# Schematic.net
KiCad netlist of a schematic drawn in EAGLE
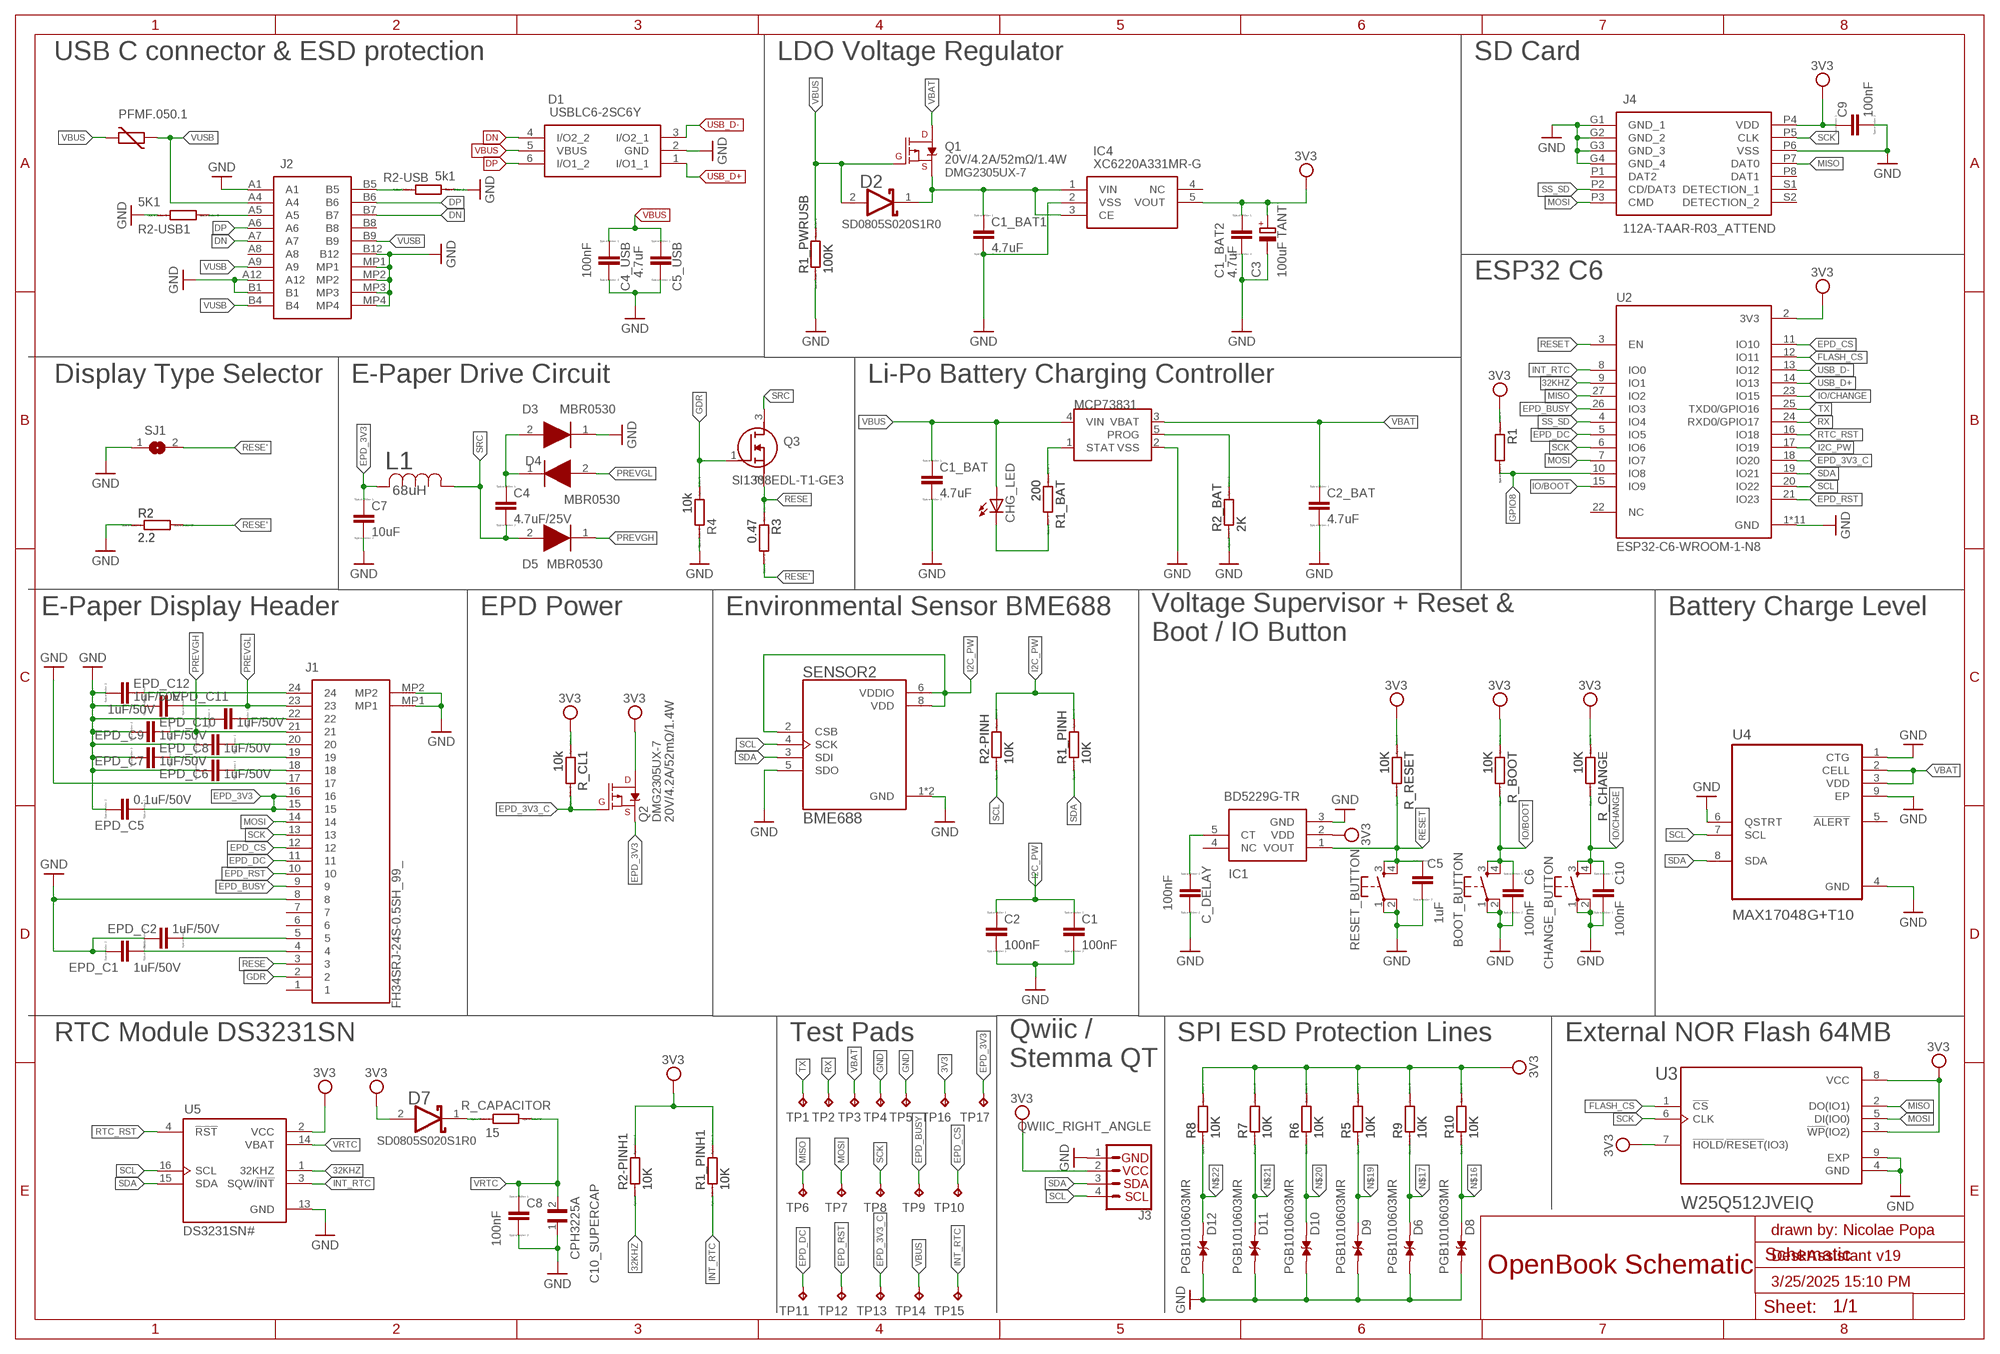
[diagram p0: schematic, sheet 1]

(export (version "E")
  (design (tool "Eeschema 10.0.6"))
  (components
    (comp (ref "BOOT_BUTTON")
      (value "BUTTON_CUSYOMV1")
      (footprint "eagle-import:MYBUTTON")
      (libsource (lib "eagle-import") (part "BUTTON_CUSYOMV1"))
    )
    (comp (ref "C1")
      (value "100nF")
      (footprint "eagle-import:EAGLE-LTSPICE_C0402")
      (libsource (lib "eagle-import") (part "EAGLE-LTSPICE_CC0402"))
    )
    (comp (ref "C1_BAT")
      (value "4.7uF")
      (footprint "eagle-import:EAGLE-LTSPICE_C0402")
      (libsource (lib "eagle-import") (part "EAGLE-LTSPICE_CC0402"))
    )
    (comp (ref "C1_BAT1")
      (value "4.7uF")
      (footprint "eagle-import:EAGLE-LTSPICE_C0402")
      (libsource (lib "eagle-import") (part "EAGLE-LTSPICE_CC0402"))
    )
    (comp (ref "C1_BAT2")
      (value "4.7uF")
      (footprint "eagle-import:EAGLE-LTSPICE_C0402")
      (libsource (lib "eagle-import") (part "EAGLE-LTSPICE_CC0402"))
    )
    (comp (ref "C2")
      (value "100nF")
      (footprint "eagle-import:EAGLE-LTSPICE_C0402")
      (libsource (lib "eagle-import") (part "EAGLE-LTSPICE_CC0402"))
    )
    (comp (ref "C2_BAT")
      (value "4.7uF")
      (footprint "eagle-import:EAGLE-LTSPICE_C0402")
      (libsource (lib "eagle-import") (part "EAGLE-LTSPICE_CC0402"))
    )
    (comp (ref "C3")
      (value "100uF TANT")
      (footprint "eagle-import:RCL_CT3528")
      (libsource (lib "eagle-import") (part "RCL_CPOL-EUCT3528"))
    )
    (comp (ref "C4")
      (value "4.7uF/25V")
      (footprint "eagle-import:EAGLE-LTSPICE_C0402")
      (libsource (lib "eagle-import") (part "EAGLE-LTSPICE_CC0402"))
    )
    (comp (ref "C4_USB")
      (value "100nF")
      (footprint "eagle-import:EAGLE-LTSPICE_C0402")
      (libsource (lib "eagle-import") (part "EAGLE-LTSPICE_CC0402"))
    )
    (comp (ref "C5")
      (value "1uF")
      (footprint "eagle-import:EAGLE-LTSPICE_C0402")
      (libsource (lib "eagle-import") (part "EAGLE-LTSPICE_CC0402"))
    )
    (comp (ref "C5_USB")
      (value "4.7uF")
      (footprint "eagle-import:EAGLE-LTSPICE_C0402")
      (libsource (lib "eagle-import") (part "EAGLE-LTSPICE_CC0402"))
    )
    (comp (ref "C6")
      (value "100nF")
      (footprint "eagle-import:EAGLE-LTSPICE_C0402")
      (libsource (lib "eagle-import") (part "EAGLE-LTSPICE_CC0402"))
    )
    (comp (ref "C7")
      (value "10uF")
      (footprint "eagle-import:EAGLE-LTSPICE_C0402")
      (libsource (lib "eagle-import") (part "EAGLE-LTSPICE_CC0402"))
    )
    (comp (ref "C8")
      (value "100nF")
      (footprint "eagle-import:EAGLE-LTSPICE_C0402")
      (libsource (lib "eagle-import") (part "EAGLE-LTSPICE_CC0402"))
    )
    (comp (ref "C9")
      (value "100nF")
      (footprint "eagle-import:ESP32_WROVER_EAGLE-LTSPICE_C0402")
      (libsource (lib "eagle-import") (part "ESP32_WROVER_EAGLE-LTSPICE_CC0402"))
    )
    (comp (ref "C10")
      (value "100nF")
      (footprint "eagle-import:EAGLE-LTSPICE_C0402")
      (libsource (lib "eagle-import") (part "EAGLE-LTSPICE_CC0402"))
    )
    (comp (ref "C10_SUPERCAP")
      (value "CPH3225A")
      (footprint "eagle-import:CAPCP3225X100N")
      (fields (field (name "MF") "Seiko Instruments"))
      (libsource (lib "eagle-import") (part "CPH3225A"))
    )
    (comp (ref "CHANGE_BUTTON")
      (value "BUTTON_CUSYOMV1")
      (footprint "eagle-import:MYBUTTON")
      (libsource (lib "eagle-import") (part "BUTTON_CUSYOMV1"))
    )
    (comp (ref "CHG_LED")
      (value "ADAFRUIT_LEDCHIP-LED0603")
      (footprint "eagle-import:ADAFRUIT_CHIP-LED0603")
      (libsource (lib "eagle-import") (part "ADAFRUIT_LEDCHIP-LED0603"))
    )
    (comp (ref "C_DELAY")
      (value "100nF")
      (footprint "eagle-import:EAGLE-LTSPICE_C0402")
      (libsource (lib "eagle-import") (part "EAGLE-LTSPICE_CC0402"))
    )
    (comp (ref "D1")
      (value "USBLC6-2SC6Y")
      (footprint "eagle-import:SOT95P280X145-6N")
      (fields (field (name "MF") "STMicroelectronics"))
      (libsource (lib "eagle-import") (part "USBLC6-2SC6Y"))
    )
    (comp (ref "D2")
      (value "ESP32_WROVER_AVX---SD0805S020S1R0_AVX_SD0805S020S1R0_0_0AVX_SD0805S020S1R0_0_0")
      (footprint "eagle-import:ESP32_WROVER_AVX---SD0805S020S1R0_AVX_SD0805S020S1R0_0")
      (fields
        (field (name "DIGIKEY_PART_NUMBER") "478-7800-1-ND")
        (field (name "MF") "AVX")
        (field (name "MOUSER_PART_NUMBER") "581-SD0805S020S1R0")
        (field (name "MANUFACTURER") "SD0805S020S1R0")
      )
      (libsource (lib "eagle-import") (part "ESP32_WROVER_AVX---SD0805S020S1R0_AVX_SD0805S020S1R0_0_0AVX_SD0805S020S1R0_0_0"))
    )
    (comp (ref "D3")
      (value "MBR0530")
      (footprint "eagle-import:SOD3716X135N")
      (fields (field (name "MF") "ON Semiconductor"))
      (libsource (lib "eagle-import") (part "MBR0530"))
    )
    (comp (ref "D4")
      (value "MBR0530")
      (footprint "eagle-import:SOD3716X135N")
      (fields (field (name "MF") "ON Semiconductor"))
      (libsource (lib "eagle-import") (part "MBR0530"))
    )
    (comp (ref "D5")
      (value "MBR0530")
      (footprint "eagle-import:SOD3716X135N")
      (fields (field (name "MF") "ON Semiconductor"))
      (libsource (lib "eagle-import") (part "MBR0530"))
    )
    (comp (ref "D6")
      (value "PGB1010603MR")
      (footprint "eagle-import:DIOC1608X36N")
      (fields (field (name "MF") "Littelfuse Inc."))
      (libsource (lib "eagle-import") (part "PGB1010603MR"))
    )
    (comp (ref "D7")
      (value "SD0805S020S1R0")
      (footprint "eagle-import:ESP32_WROVER_AVX---SD0805S020S1R0_AVX_SD0805S020S1R0_0")
      (fields
        (field (name "DIGIKEY_PART_NUMBER") "478-7800-1-ND")
        (field (name "MF") "AVX")
        (field (name "MOUSER_PART_NUMBER") "581-SD0805S020S1R0")
        (field (name "MANUFACTURER") "SD0805S020S1R0")
      )
      (libsource (lib "eagle-import") (part "ESP32_WROVER_AVX---SD0805S020S1R0_AVX_SD0805S020S1R0_0_0AVX_SD0805S020S1R0_0_0"))
    )
    (comp (ref "D8")
      (value "PGB1010603MR")
      (footprint "eagle-import:DIOC1608X36N")
      (fields (field (name "MF") "Littelfuse Inc."))
      (libsource (lib "eagle-import") (part "PGB1010603MR"))
    )
    (comp (ref "D9")
      (value "PGB1010603MR")
      (footprint "eagle-import:DIOC1608X36N")
      (fields (field (name "MF") "Littelfuse Inc."))
      (libsource (lib "eagle-import") (part "PGB1010603MR"))
    )
    (comp (ref "D10")
      (value "PGB1010603MR")
      (footprint "eagle-import:DIOC1608X36N")
      (fields (field (name "MF") "Littelfuse Inc."))
      (libsource (lib "eagle-import") (part "PGB1010603MR"))
    )
    (comp (ref "D11")
      (value "PGB1010603MR")
      (footprint "eagle-import:DIOC1608X36N")
      (fields (field (name "MF") "Littelfuse Inc."))
      (libsource (lib "eagle-import") (part "PGB1010603MR"))
    )
    (comp (ref "D12")
      (value "PGB1010603MR")
      (footprint "eagle-import:DIOC1608X36N")
      (fields (field (name "MF") "Littelfuse Inc."))
      (libsource (lib "eagle-import") (part "PGB1010603MR"))
    )
    (comp (ref "EPD_C1")
      (value "1uF/50V")
      (footprint "eagle-import:EAGLE-LTSPICE_C0402")
      (libsource (lib "eagle-import") (part "EAGLE-LTSPICE_CC0402"))
    )
    (comp (ref "EPD_C2")
      (value "1uF/50V")
      (footprint "eagle-import:EAGLE-LTSPICE_C0402")
      (libsource (lib "eagle-import") (part "EAGLE-LTSPICE_CC0402"))
    )
    (comp (ref "EPD_C5")
      (value "0.1uF/50V")
      (footprint "eagle-import:EAGLE-LTSPICE_C0402")
      (libsource (lib "eagle-import") (part "EAGLE-LTSPICE_CC0402"))
    )
    (comp (ref "EPD_C6")
      (value "1uF/50V")
      (footprint "eagle-import:EAGLE-LTSPICE_C0402")
      (libsource (lib "eagle-import") (part "EAGLE-LTSPICE_CC0402"))
    )
    (comp (ref "EPD_C7")
      (value "1uF/50V")
      (footprint "eagle-import:EAGLE-LTSPICE_C0402")
      (libsource (lib "eagle-import") (part "EAGLE-LTSPICE_CC0402"))
    )
    (comp (ref "EPD_C8")
      (value "1uF/50V")
      (footprint "eagle-import:EAGLE-LTSPICE_C0402")
      (libsource (lib "eagle-import") (part "EAGLE-LTSPICE_CC0402"))
    )
    (comp (ref "EPD_C9")
      (value "1uF/50V")
      (footprint "eagle-import:EAGLE-LTSPICE_C0402")
      (libsource (lib "eagle-import") (part "EAGLE-LTSPICE_CC0402"))
    )
    (comp (ref "EPD_C10")
      (value "1uF/50V")
      (footprint "eagle-import:EAGLE-LTSPICE_C0402")
      (libsource (lib "eagle-import") (part "EAGLE-LTSPICE_CC0402"))
    )
    (comp (ref "EPD_C11")
      (value "1uF/50V")
      (footprint "eagle-import:EAGLE-LTSPICE_C0402")
      (libsource (lib "eagle-import") (part "EAGLE-LTSPICE_CC0402"))
    )
    (comp (ref "EPD_C12")
      (value "1uF/50V")
      (footprint "eagle-import:EAGLE-LTSPICE_C0402")
      (libsource (lib "eagle-import") (part "EAGLE-LTSPICE_CC0402"))
    )
    (comp (ref "IC1")
      (value "BD5229G-TR")
      (footprint "eagle-import:SOT95P280X125-5N")
      (fields (field (name "MOUSER_PART_NUMBER") "755-BD5229G-TR"))
      (libsource (lib "eagle-import") (part "BD5229G-TR"))
    )
    (comp (ref "IC4")
      (value "XC6220A331MR-G")
      (footprint "eagle-import:SOT95P280X120-5N")
      (fields (field (name "MOUSER_PART_NUMBER") "865-XC6220A331MR-G"))
      (libsource (lib "eagle-import") (part "XC6220A331MR-G"))
    )
    (comp (ref "J1")
      (value "FH34SRJ-24S-0.5SH_99_")
      (footprint "eagle-import:FH34SRJ24S05SH99")
      (fields
        (field (name "MANUFACTURER_PART_NUMBER") "FH34SRJ-24S-0.5SH(99)")
        (field (name "MOUSER_PART_NUMBER") "798-FH34SRJ24S05SH99")
      )
      (libsource (lib "eagle-import") (part "FH34SRJ-24S-0.5SH_99_"))
    )
    (comp (ref "J2")
      (value "SAMACSYS_PARTS_USB4110-GF-A")
      (footprint "eagle-import:SAMACSYS_PARTS_USB4110GFA")
      (fields
        (field (name "MANUFACTURER_PART_NUMBER") "USB4110-GF-A")
        (field (name "MOUSER_PART_NUMBER") "640-USB4110-GF-A")
      )
      (libsource (lib "eagle-import") (part "SAMACSYS_PARTS_USB4110-GF-A"))
    )
    (comp (ref "J3")
      (value "QWIIC_RIGHT_ANGLE")
      (footprint "eagle-import:JST04_1MM_RA")
      (libsource (lib "eagle-import") (part "QWIIC_CONNECTORJS-1MM"))
    )
    (comp (ref "J4")
      (value "112A-TAAR-R03_ATTEND")
      (footprint "eagle-import:112ATAARR03ATTEND")
      (fields (field (name "MANUFACTURER_PART_NUMBER") "112A-TAAR-R03 ATTEND"))
      (libsource (lib "eagle-import") (part "112A-TAAR-R03_ATTEND"))
    )
    (comp (ref "L1")
      (value "68uH")
      (footprint "eagle-import:IND_4828-WE-TPC_WRE")
      (fields
        (field (name "MANUFACTURER_PART_NUMBER") "744043680")
        (field (name "COPYRIGHT") "Copyright (C) 2024 Ultra Librarian. All rights reserved.")
      )
      (libsource (lib "eagle-import") (part "744043680IND_4828-WE-TPC_WRE"))
    )
    (comp (ref "PFMF.050.1")
      (value "ESP32C6_VARISTORCN1812")
      (footprint "eagle-import:ESP32C6_VARISTOR_CT_CN1812")
      (libsource (lib "eagle-import") (part "ESP32C6_VARISTORCN1812"))
    )
    (comp (ref "Q1")
      (value "20V/4.2A/52mΩ/1.4W")
      (footprint "eagle-import:ESP32_WROVER_SPARKFUN-DISCRETESEMI_SOT23-3")
      (fields (field (name "MANUFACTURER") "DMG2305UX-7"))
      (libsource (lib "eagle-import") (part "ESP32_WROVER_SPARKFUN-DISCRETESEMI_MOSFET_PCH-DMG2305UX-7"))
    )
    (comp (ref "Q2")
      (value "20V/4.2A/52mΩ/1.4W")
      (footprint "eagle-import:ESP32_WROVER_SPARKFUN-DISCRETESEMI_SOT23-3")
      (fields (field (name "MANUFACTURER") "DMG2305UX-7"))
      (libsource (lib "eagle-import") (part "ESP32_WROVER_SPARKFUN-DISCRETESEMI_MOSFET_PCH-DMG2305UX-7"))
    )
    (comp (ref "Q3")
      (value "SI1308EDL-T1-GE3")
      (footprint "eagle-import:SOT65P210X110-3N")
      (fields (field (name "MF") "Vishay Siliconix"))
      (libsource (lib "eagle-import") (part "SI1308EDL-T1-GE3"))
    )
    (comp (ref "R1")
      (value "ESP32_WROVER_EAGLE-LTSPICE_RR0402")
      (footprint "eagle-import:ESP32_WROVER_EAGLE-LTSPICE_R0402")
      (libsource (lib "eagle-import") (part "ESP32_WROVER_EAGLE-LTSPICE_RR0402"))
    )
    (comp (ref "R1_BAT")
      (value "200")
      (footprint "eagle-import:ESP32_WROVER_EAGLE-LTSPICE_R0402")
      (libsource (lib "eagle-import") (part "ESP32_WROVER_EAGLE-LTSPICE_RR0402"))
    )
    (comp (ref "R1_PINH")
      (value "10K")
      (footprint "eagle-import:ESP32_WROVER_EAGLE-LTSPICE_R0402")
      (libsource (lib "eagle-import") (part "ESP32_WROVER_EAGLE-LTSPICE_RR0402"))
    )
    (comp (ref "R1_PINH1")
      (value "10K")
      (footprint "eagle-import:ESP32_WROVER_EAGLE-LTSPICE_R0402")
      (libsource (lib "eagle-import") (part "ESP32_WROVER_EAGLE-LTSPICE_RR0402"))
    )
    (comp (ref "R1_PWRUSB")
      (value "100K")
      (footprint "eagle-import:ESP32_WROVER_EAGLE-LTSPICE_R0402")
      (libsource (lib "eagle-import") (part "ESP32_WROVER_EAGLE-LTSPICE_RR0402"))
    )
    (comp (ref "R2")
      (value "2.2")
      (footprint "eagle-import:ESP32_WROVER_EAGLE-LTSPICE_R0402")
      (libsource (lib "eagle-import") (part "ESP32_WROVER_EAGLE-LTSPICE_RR0402"))
    )
    (comp (ref "R2-PINH")
      (value "10K")
      (footprint "eagle-import:ESP32_WROVER_EAGLE-LTSPICE_R0402")
      (libsource (lib "eagle-import") (part "ESP32_WROVER_EAGLE-LTSPICE_RR0402"))
    )
    (comp (ref "R2-PINH1")
      (value "10K")
      (footprint "eagle-import:ESP32_WROVER_EAGLE-LTSPICE_R0402")
      (libsource (lib "eagle-import") (part "ESP32_WROVER_EAGLE-LTSPICE_RR0402"))
    )
    (comp (ref "R2-USB")
      (value "5k1")
      (footprint "eagle-import:ESP32_WROVER_EAGLE-LTSPICE_R0402")
      (libsource (lib "eagle-import") (part "ESP32_WROVER_EAGLE-LTSPICE_RR0402"))
    )
    (comp (ref "R2-USB1")
      (value "5K1")
      (footprint "eagle-import:ESP32_WROVER_EAGLE-LTSPICE_R0402")
      (libsource (lib "eagle-import") (part "ESP32_WROVER_EAGLE-LTSPICE_RR0402"))
    )
    (comp (ref "R2_BAT")
      (value "2K")
      (footprint "eagle-import:ESP32_WROVER_EAGLE-LTSPICE_R0402")
      (libsource (lib "eagle-import") (part "ESP32_WROVER_EAGLE-LTSPICE_RR0402"))
    )
    (comp (ref "R3")
      (value "0.47")
      (footprint "eagle-import:ESP32_WROVER_EAGLE-LTSPICE_R0402")
      (libsource (lib "eagle-import") (part "ESP32_WROVER_EAGLE-LTSPICE_RR0402"))
    )
    (comp (ref "R4")
      (value "10k")
      (footprint "eagle-import:ESP32_WROVER_EAGLE-LTSPICE_R0402")
      (libsource (lib "eagle-import") (part "ESP32_WROVER_EAGLE-LTSPICE_RR0402"))
    )
    (comp (ref "R5")
      (value "10K")
      (footprint "eagle-import:ESP32_WROVER_EAGLE-LTSPICE_R0402")
      (libsource (lib "eagle-import") (part "ESP32_WROVER_EAGLE-LTSPICE_RR0402"))
    )
    (comp (ref "R6")
      (value "10K")
      (footprint "eagle-import:ESP32_WROVER_EAGLE-LTSPICE_R0402")
      (libsource (lib "eagle-import") (part "ESP32_WROVER_EAGLE-LTSPICE_RR0402"))
    )
    (comp (ref "R7")
      (value "10K")
      (footprint "eagle-import:ESP32_WROVER_EAGLE-LTSPICE_R0402")
      (libsource (lib "eagle-import") (part "ESP32_WROVER_EAGLE-LTSPICE_RR0402"))
    )
    (comp (ref "R8")
      (value "10K")
      (footprint "eagle-import:ESP32_WROVER_EAGLE-LTSPICE_R0402")
      (libsource (lib "eagle-import") (part "ESP32_WROVER_EAGLE-LTSPICE_RR0402"))
    )
    (comp (ref "R9")
      (value "10K")
      (footprint "eagle-import:ESP32_WROVER_EAGLE-LTSPICE_R0402")
      (libsource (lib "eagle-import") (part "ESP32_WROVER_EAGLE-LTSPICE_RR0402"))
    )
    (comp (ref "R10")
      (value "10K")
      (footprint "eagle-import:ESP32_WROVER_EAGLE-LTSPICE_R0402")
      (libsource (lib "eagle-import") (part "ESP32_WROVER_EAGLE-LTSPICE_RR0402"))
    )
    (comp (ref "RESET_BUTTON")
      (value "BUTTON_CUSYOMV1")
      (footprint "eagle-import:MYBUTTON")
      (libsource (lib "eagle-import") (part "BUTTON_CUSYOMV1"))
    )
    (comp (ref "R_BOOT")
      (value "10K")
      (footprint "eagle-import:ESP32_WROVER_EAGLE-LTSPICE_R0402")
      (libsource (lib "eagle-import") (part "ESP32_WROVER_EAGLE-LTSPICE_RR0402"))
    )
    (comp (ref "R_CAPACITOR")
      (value "15")
      (footprint "eagle-import:ESP32_WROVER_EAGLE-LTSPICE_R0402")
      (libsource (lib "eagle-import") (part "ESP32_WROVER_EAGLE-LTSPICE_RR0402"))
    )
    (comp (ref "R_CHANGE")
      (value "10K")
      (footprint "eagle-import:ESP32_WROVER_EAGLE-LTSPICE_R0402")
      (libsource (lib "eagle-import") (part "ESP32_WROVER_EAGLE-LTSPICE_RR0402"))
    )
    (comp (ref "R_CL1")
      (value "10k")
      (footprint "eagle-import:ESP32_WROVER_EAGLE-LTSPICE_R0402")
      (libsource (lib "eagle-import") (part "ESP32_WROVER_EAGLE-LTSPICE_RR0402"))
    )
    (comp (ref "R_RESET")
      (value "10K")
      (footprint "eagle-import:ESP32_WROVER_EAGLE-LTSPICE_R0402")
      (libsource (lib "eagle-import") (part "ESP32_WROVER_EAGLE-LTSPICE_RR0402"))
    )
    (comp (ref "SENSOR2")
      (value "BME688")
      (footprint "eagle-import:ESP32_WROVER_BME680_PSON80P300X300X100-8N")
      (fields (field (name "MF") "Bosch Sensortec") (field (name "MP") "BME680"))
      (libsource (lib "eagle-import") (part "ESP32_WROVER_BME680_BME680"))
    )
    (comp (ref "SJ1") (value "SJ") (footprint "eagle-import:SJ") (libsource (lib "eagle-import") (part "SJ")))
    (comp (ref "TP1")
      (value "TPTP20R")
      (footprint "eagle-import:TP20R")
      (libsource (lib "eagle-import") (part "TPTP20R"))
    )
    (comp (ref "TP2")
      (value "TPTP20R")
      (footprint "eagle-import:TP20R")
      (libsource (lib "eagle-import") (part "TPTP20R"))
    )
    (comp (ref "TP3")
      (value "TPTP20R")
      (footprint "eagle-import:TP20R")
      (libsource (lib "eagle-import") (part "TPTP20R"))
    )
    (comp (ref "TP4")
      (value "TPTP20R")
      (footprint "eagle-import:TP20R")
      (libsource (lib "eagle-import") (part "TPTP20R"))
    )
    (comp (ref "TP5")
      (value "TPTP20R")
      (footprint "eagle-import:TP20R")
      (libsource (lib "eagle-import") (part "TPTP20R"))
    )
    (comp (ref "TP6")
      (value "TPTP20R")
      (footprint "eagle-import:TP20R")
      (libsource (lib "eagle-import") (part "TPTP20R"))
    )
    (comp (ref "TP7")
      (value "TPTP20R")
      (footprint "eagle-import:TP20R")
      (libsource (lib "eagle-import") (part "TPTP20R"))
    )
    (comp (ref "TP8")
      (value "TPTP20R")
      (footprint "eagle-import:TP20R")
      (libsource (lib "eagle-import") (part "TPTP20R"))
    )
    (comp (ref "TP9")
      (value "TPTP20R")
      (footprint "eagle-import:TP20R")
      (libsource (lib "eagle-import") (part "TPTP20R"))
    )
    (comp (ref "TP10")
      (value "TPTP20R")
      (footprint "eagle-import:TP20R")
      (libsource (lib "eagle-import") (part "TPTP20R"))
    )
    (comp (ref "TP11")
      (value "TPTP20R")
      (footprint "eagle-import:TP20R")
      (libsource (lib "eagle-import") (part "TPTP20R"))
    )
    (comp (ref "TP12")
      (value "TPTP20R")
      (footprint "eagle-import:TP20R")
      (libsource (lib "eagle-import") (part "TPTP20R"))
    )
    (comp (ref "TP13")
      (value "TPTP20R")
      (footprint "eagle-import:TP20R")
      (libsource (lib "eagle-import") (part "TPTP20R"))
    )
    (comp (ref "TP14")
      (value "TPTP20R")
      (footprint "eagle-import:TP20R")
      (libsource (lib "eagle-import") (part "TPTP20R"))
    )
    (comp (ref "TP15")
      (value "TPTP20R")
      (footprint "eagle-import:TP20R")
      (libsource (lib "eagle-import") (part "TPTP20R"))
    )
    (comp (ref "TP16")
      (value "TPTP20R")
      (footprint "eagle-import:TP20R")
      (libsource (lib "eagle-import") (part "TPTP20R"))
    )
    (comp (ref "TP17")
      (value "TPTP20R")
      (footprint "eagle-import:TP20R")
      (libsource (lib "eagle-import") (part "TPTP20R"))
    )
    (comp (ref "U1")
      (value "MCP73831")
      (footprint "eagle-import:ESP32_WROVER_SPARKFUN-IC-POWER_SOT23-5")
      (libsource (lib "eagle-import") (part "ESP32_WROVER_SPARKFUN-IC-POWER_MCP73831"))
    )
    (comp (ref "U2")
      (value "ESP32-C6-WROOM-1-N8")
      (footprint "eagle-import:XCVR_ESP32-C6-WROOM-1-N8")
      (fields (field (name "MF") "Espressif Systems"))
      (libsource (lib "eagle-import") (part "ESP32-C6-WROOM-1-N8"))
    )
    (comp (ref "U3")
      (value "W25Q512JVEIQ")
      (footprint "eagle-import:SON127P600X800X80-9N")
      (fields (field (name "MF") "Winbond Electronics"))
      (libsource (lib "eagle-import") (part "W25Q512JVEIQ"))
    )
    (comp (ref "U4")
      (value "MAX17048G+T10")
      (footprint "eagle-import:SON50P200X200X80-9N")
      (fields (field (name "MF") "Analog Devices"))
      (libsource (lib "eagle-import") (part "MAX17048G+T10"))
    )
    (comp (ref "U5")
      (value "DS3231SN#")
      (footprint "eagle-import:SOIC127P1032X265-16N")
      (fields (field (name "MF") "Analog Devices"))
      (libsource (lib "eagle-import") (part "DS3231SN#"))
    )
  )
  (nets
    (net (code "1") (name "3V3") (class "Default")
      (node (ref "C1_BAT2") (pin "1") (pinfunction "1_1") (pintype "passive"))
      (node (ref "C3") (pin "+") (pinfunction "+_+") (pintype "passive"))
      (node (ref "C9") (pin "1") (pinfunction "1_1") (pintype "passive"))
      (node (ref "D7") (pin "2") (pinfunction "ANODE_2") (pintype "bidirectional"))
      (node (ref "IC1") (pin "2") (pinfunction "VDD_2") (pintype "bidirectional"))
      (node (ref "IC4") (pin "5") (pinfunction "VOUT_5") (pintype "bidirectional"))
      (node (ref "J3") (pin "2") (pinfunction "2_2") (pintype "power_in"))
      (node (ref "J4") (pin "P4") (pinfunction "VDD_P4") (pintype "bidirectional"))
      (node (ref "Q2") (pin "3") (pinfunction "D_3") (pintype "bidirectional"))
      (node (ref "R1") (pin "1") (pinfunction "1_1") (pintype "passive"))
      (node (ref "R10") (pin "2") (pinfunction "2_2") (pintype "passive"))
      (node (ref "R1_PINH1") (pin "2") (pinfunction "2_2") (pintype "passive"))
      (node (ref "R2-PINH1") (pin "2") (pinfunction "2_2") (pintype "passive"))
      (node (ref "R5") (pin "2") (pinfunction "2_2") (pintype "passive"))
      (node (ref "R6") (pin "2") (pinfunction "2_2") (pintype "passive"))
      (node (ref "R7") (pin "2") (pinfunction "2_2") (pintype "passive"))
      (node (ref "R8") (pin "2") (pinfunction "2_2") (pintype "passive"))
      (node (ref "R9") (pin "2") (pinfunction "2_2") (pintype "passive"))
      (node (ref "R_BOOT") (pin "1") (pinfunction "1_1") (pintype "passive"))
      (node (ref "R_CHANGE") (pin "1") (pinfunction "1_1") (pintype "passive"))
      (node (ref "R_CL1") (pin "1") (pinfunction "1_1") (pintype "passive"))
      (node (ref "R_RESET") (pin "1") (pinfunction "1_1") (pintype "passive"))
      (node (ref "TP16") (pin "TP") (pinfunction "TP_TP") (pintype "input"))
      (node (ref "U2") (pin "2") (pinfunction "3V3_2") (pintype "power_in"))
      (node (ref "U3") (pin "3") (pinfunction "~{WP}(IO2)_3") (pintype "bidirectional"))
      (node (ref "U3") (pin "7") (pinfunction "~{HOLD}/~{RESET}(IO3)_7") (pintype "bidirectional"))
      (node (ref "U3") (pin "8") (pinfunction "VCC_8") (pintype "power_in"))
      (node (ref "U5") (pin "2") (pinfunction "VCC_2") (pintype "power_in"))
    )
    (net (code "2") (name "32KHZ") (class "Default")
      (node (ref "R2-PINH1") (pin "1") (pinfunction "1_1") (pintype "passive"))
      (node (ref "U2") (pin "9") (pinfunction "IO1_9") (pintype "bidirectional"))
      (node (ref "U5") (pin "1") (pinfunction "32KHZ_1") (pintype "output"))
    )
    (net (code "3") (name "DN") (class "Default")
      (node (ref "D1") (pin "4") (pinfunction "I/O2_2_4") (pintype "bidirectional"))
      (node (ref "J2") (pin "A7") (pinfunction "A7_A7") (pintype "bidirectional"))
      (node (ref "J2") (pin "B7") (pinfunction "B7_B7") (pintype "bidirectional"))
    )
    (net (code "4") (name "DP") (class "Default")
      (node (ref "D1") (pin "6") (pinfunction "I/O1_2_6") (pintype "bidirectional"))
      (node (ref "J2") (pin "A6") (pinfunction "A6_A6") (pintype "bidirectional"))
      (node (ref "J2") (pin "B6") (pinfunction "B6_B6") (pintype "bidirectional"))
    )
    (net (code "5") (name "EPD_3V3") (class "Default")
      (node (ref "C7") (pin "1") (pinfunction "1_1") (pintype "passive"))
      (node (ref "EPD_C5") (pin "1") (pinfunction "1_1") (pintype "passive"))
      (node (ref "J1") (pin "15") (pinfunction "15_15") (pintype "bidirectional"))
      (node (ref "J1") (pin "16") (pinfunction "16_16") (pintype "bidirectional"))
      (node (ref "L1") (pin "2") (pinfunction "2_2") (pintype "passive"))
      (node (ref "Q2") (pin "2") (pinfunction "S_2") (pintype "bidirectional"))
      (node (ref "TP17") (pin "TP") (pinfunction "TP_TP") (pintype "input"))
    )
    (net (code "6") (name "EPD_3V3_C") (class "Default")
      (node (ref "Q2") (pin "1") (pinfunction "G_1") (pintype "bidirectional"))
      (node (ref "R_CL1") (pin "2") (pinfunction "2_2") (pintype "passive"))
      (node (ref "TP13") (pin "TP") (pinfunction "TP_TP") (pintype "input"))
      (node (ref "U2") (pin "18") (pinfunction "IO20_18") (pintype "bidirectional"))
    )
    (net (code "7") (name "EPD_BUSY") (class "Default")
      (node (ref "J1") (pin "9") (pinfunction "9_9") (pintype "bidirectional"))
      (node (ref "TP9") (pin "TP") (pinfunction "TP_TP") (pintype "input"))
      (node (ref "U2") (pin "26") (pinfunction "IO3_26") (pintype "bidirectional"))
    )
    (net (code "8") (name "EPD_CS") (class "Default")
      (node (ref "J1") (pin "12") (pinfunction "12_12") (pintype "bidirectional"))
      (node (ref "TP10") (pin "TP") (pinfunction "TP_TP") (pintype "input"))
      (node (ref "U2") (pin "11") (pinfunction "IO10_11") (pintype "bidirectional"))
    )
    (net (code "9") (name "EPD_DC") (class "Default")
      (node (ref "J1") (pin "11") (pinfunction "11_11") (pintype "bidirectional"))
      (node (ref "TP11") (pin "TP") (pinfunction "TP_TP") (pintype "input"))
      (node (ref "U2") (pin "5") (pinfunction "IO5_5") (pintype "bidirectional"))
    )
    (net (code "10") (name "EPD_RST") (class "Default")
      (node (ref "J1") (pin "10") (pinfunction "10_10") (pintype "bidirectional"))
      (node (ref "TP12") (pin "TP") (pinfunction "TP_TP") (pintype "input"))
      (node (ref "U2") (pin "21") (pinfunction "IO23_21") (pintype "bidirectional"))
    )
    (net (code "11") (name "FLASH_CS") (class "Default")
      (node (ref "U2") (pin "12") (pinfunction "IO11_12") (pintype "bidirectional"))
      (node (ref "U3") (pin "1") (pinfunction "~{CS}_1") (pintype "input"))
    )
    (net (code "12") (name "GDR") (class "Default")
      (node (ref "J1") (pin "2") (pinfunction "2_2") (pintype "bidirectional"))
      (node (ref "Q3") (pin "1") (pinfunction "G_1") (pintype "bidirectional"))
      (node (ref "R4") (pin "1") (pinfunction "1_1") (pintype "passive"))
    )
    (net (code "13") (name "GND") (class "Default")
      (node (ref "BOOT_BUTTON") (pin "1") (pinfunction "1_1") (pintype "passive"))
      (node (ref "BOOT_BUTTON") (pin "2") (pinfunction "2_2") (pintype "passive"))
      (node (ref "C1") (pin "2") (pinfunction "2_2") (pintype "passive"))
      (node (ref "C10") (pin "2") (pinfunction "2_2") (pintype "passive"))
      (node (ref "C10_SUPERCAP") (pin "1") (pinfunction "1_1") (pintype "passive"))
      (node (ref "C1_BAT") (pin "2") (pinfunction "2_2") (pintype "passive"))
      (node (ref "C1_BAT1") (pin "2") (pinfunction "2_2") (pintype "passive"))
      (node (ref "C1_BAT2") (pin "2") (pinfunction "2_2") (pintype "passive"))
      (node (ref "C2") (pin "2") (pinfunction "2_2") (pintype "passive"))
      (node (ref "C2_BAT") (pin "2") (pinfunction "2_2") (pintype "passive"))
      (node (ref "C3") (pin "-") (pinfunction "-_-") (pintype "passive"))
      (node (ref "C4_USB") (pin "2") (pinfunction "2_2") (pintype "passive"))
      (node (ref "C5") (pin "2") (pinfunction "2_2") (pintype "passive"))
      (node (ref "C5_USB") (pin "2") (pinfunction "2_2") (pintype "passive"))
      (node (ref "C6") (pin "2") (pinfunction "2_2") (pintype "passive"))
      (node (ref "C7") (pin "2") (pinfunction "2_2") (pintype "passive"))
      (node (ref "C8") (pin "2") (pinfunction "2_2") (pintype "passive"))
      (node (ref "C9") (pin "2") (pinfunction "2_2") (pintype "passive"))
      (node (ref "CHANGE_BUTTON") (pin "1") (pinfunction "1_1") (pintype "passive"))
      (node (ref "CHANGE_BUTTON") (pin "2") (pinfunction "2_2") (pintype "passive"))
      (node (ref "C_DELAY") (pin "2") (pinfunction "2_2") (pintype "passive"))
      (node (ref "D1") (pin "2") (pinfunction "GND_2") (pintype "bidirectional"))
      (node (ref "D10") (pin "1") (pinfunction "1_1") (pintype "passive"))
      (node (ref "D11") (pin "1") (pinfunction "1_1") (pintype "passive"))
      (node (ref "D12") (pin "1") (pinfunction "1_1") (pintype "passive"))
      (node (ref "D3") (pin "1") (pinfunction "K_1") (pintype "bidirectional"))
      (node (ref "D6") (pin "1") (pinfunction "1_1") (pintype "passive"))
      (node (ref "D8") (pin "1") (pinfunction "1_1") (pintype "passive"))
      (node (ref "D9") (pin "1") (pinfunction "1_1") (pintype "passive"))
      (node (ref "EPD_C1") (pin "2") (pinfunction "2_2") (pintype "passive"))
      (node (ref "EPD_C10") (pin "2") (pinfunction "2_2") (pintype "passive"))
      (node (ref "EPD_C11") (pin "2") (pinfunction "2_2") (pintype "passive"))
      (node (ref "EPD_C12") (pin "2") (pinfunction "2_2") (pintype "passive"))
      (node (ref "EPD_C2") (pin "2") (pinfunction "2_2") (pintype "passive"))
      (node (ref "EPD_C5") (pin "2") (pinfunction "2_2") (pintype "passive"))
      (node (ref "EPD_C6") (pin "2") (pinfunction "2_2") (pintype "passive"))
      (node (ref "EPD_C7") (pin "2") (pinfunction "2_2") (pintype "passive"))
      (node (ref "EPD_C8") (pin "2") (pinfunction "2_2") (pintype "passive"))
      (node (ref "EPD_C9") (pin "2") (pinfunction "2_2") (pintype "passive"))
      (node (ref "IC1") (pin "3") (pinfunction "GND_3") (pintype "bidirectional"))
      (node (ref "IC4") (pin "2") (pinfunction "VSS_2") (pintype "bidirectional"))
      (node (ref "J1") (pin "17") (pinfunction "17_17") (pintype "bidirectional"))
      (node (ref "J1") (pin "8") (pinfunction "8_8") (pintype "bidirectional"))
      (node (ref "J1") (pin "MP1") (pinfunction "MP1_MP1") (pintype "bidirectional"))
      (node (ref "J1") (pin "MP2") (pinfunction "MP2_MP2") (pintype "bidirectional"))
      (node (ref "J2") (pin "A1") (pinfunction "A1_A1") (pintype "bidirectional"))
      (node (ref "J2") (pin "A12") (pinfunction "A12_A12") (pintype "bidirectional"))
      (node (ref "J2") (pin "B1") (pinfunction "B1_B1") (pintype "bidirectional"))
      (node (ref "J2") (pin "B12") (pinfunction "B12_B12") (pintype "bidirectional"))
      (node (ref "J2") (pin "MP1") (pinfunction "MP1_MP1") (pintype "bidirectional"))
      (node (ref "J2") (pin "MP2") (pinfunction "MP2_MP2") (pintype "bidirectional"))
      (node (ref "J2") (pin "MP3") (pinfunction "MP3_MP3") (pintype "bidirectional"))
      (node (ref "J2") (pin "MP4") (pinfunction "MP4_MP4") (pintype "bidirectional"))
      (node (ref "J3") (pin "1") (pinfunction "1_1") (pintype "power_in"))
      (node (ref "J4") (pin "G1") (pinfunction "GND_1_G1") (pintype "bidirectional"))
      (node (ref "J4") (pin "G2") (pinfunction "GND_2_G2") (pintype "bidirectional"))
      (node (ref "J4") (pin "G3") (pinfunction "GND_3_G3") (pintype "bidirectional"))
      (node (ref "J4") (pin "G4") (pinfunction "GND_4_G4") (pintype "bidirectional"))
      (node (ref "J4") (pin "P6") (pinfunction "VSS_P6") (pintype "bidirectional"))
      (node (ref "R1_PWRUSB") (pin "1") (pinfunction "1_1") (pintype "passive"))
      (node (ref "R2") (pin "1") (pinfunction "1_1") (pintype "passive"))
      (node (ref "R2-USB") (pin "2") (pinfunction "2_2") (pintype "passive"))
      (node (ref "R2-USB1") (pin "1") (pinfunction "1_1") (pintype "passive"))
      (node (ref "R2_BAT") (pin "1") (pinfunction "1_1") (pintype "passive"))
      (node (ref "R4") (pin "2") (pinfunction "2_2") (pintype "passive"))
      (node (ref "RESET_BUTTON") (pin "1") (pinfunction "1_1") (pintype "passive"))
      (node (ref "RESET_BUTTON") (pin "2") (pinfunction "2_2") (pintype "passive"))
      (node (ref "SENSOR2") (pin "1") (pinfunction "GND_1") (pintype "power_in"))
      (node (ref "SENSOR2") (pin "5") (pinfunction "SDO_5") (pintype "bidirectional"))
      (node (ref "SENSOR2") (pin "7") (pinfunction "GND_7") (pintype "power_in"))
      (node (ref "SJ1") (pin "1") (pinfunction "1_1") (pintype "passive"))
      (node (ref "TP4") (pin "TP") (pinfunction "TP_TP") (pintype "input"))
      (node (ref "TP5") (pin "TP") (pinfunction "TP_TP") (pintype "input"))
      (node (ref "U1") (pin "2") (pinfunction "VSS_2") (pintype "power_in"))
      (node (ref "U2") (pin "1") (pinfunction "GND_1") (pintype "power_in"))
      (node (ref "U2") (pin "28") (pinfunction "GND_28") (pintype "power_in"))
      (node (ref "U2") (pin "29_1") (pinfunction "GND_29_1") (pintype "power_in"))
      (node (ref "U2") (pin "29_2") (pinfunction "GND_29_2") (pintype "power_in"))
      (node (ref "U2") (pin "29_3") (pinfunction "GND_29_3") (pintype "power_in"))
      (node (ref "U2") (pin "29_4") (pinfunction "GND_29_4") (pintype "power_in"))
      (node (ref "U2") (pin "29_5") (pinfunction "GND_29_5") (pintype "power_in"))
      (node (ref "U2") (pin "29_6") (pinfunction "GND_29_6") (pintype "power_in"))
      (node (ref "U2") (pin "29_7") (pinfunction "GND_29_7") (pintype "power_in"))
      (node (ref "U2") (pin "29_8") (pinfunction "GND_29_8") (pintype "power_in"))
      (node (ref "U2") (pin "29_9") (pinfunction "GND_29_9") (pintype "power_in"))
      (node (ref "U3") (pin "4") (pinfunction "GND_4") (pintype "power_in"))
      (node (ref "U3") (pin "9") (pinfunction "EXP_9") (pintype "passive"))
      (node (ref "U4") (pin "1") (pinfunction "CTG_1") (pintype "power_in"))
      (node (ref "U4") (pin "4") (pinfunction "GND_4") (pintype "power_in"))
      (node (ref "U4") (pin "6") (pinfunction "QSTRT_6") (pintype "input"))
      (node (ref "U4") (pin "9") (pinfunction "EP_9") (pintype "power_in"))
      (node (ref "U5") (pin "13") (pinfunction "GND_13") (pintype "power_in"))
    )
    (net (code "14") (name "GPIO8") (class "Default")
      (node (ref "R1") (pin "2") (pinfunction "2_2") (pintype "passive"))
      (node (ref "U2") (pin "10") (pinfunction "IO8_10") (pintype "bidirectional"))
    )
    (net (code "15") (name "I2C_PW") (class "Default")
      (node (ref "C1") (pin "1") (pinfunction "1_1") (pintype "passive"))
      (node (ref "C2") (pin "1") (pinfunction "1_1") (pintype "passive"))
      (node (ref "R1_PINH") (pin "2") (pinfunction "2_2") (pintype "passive"))
      (node (ref "R2-PINH") (pin "2") (pinfunction "2_2") (pintype "passive"))
      (node (ref "SENSOR2") (pin "2") (pinfunction "CSB_2") (pintype "input"))
      (node (ref "SENSOR2") (pin "6") (pinfunction "VDDIO_6") (pintype "power_in"))
      (node (ref "SENSOR2") (pin "8") (pinfunction "VDD_8") (pintype "power_in"))
      (node (ref "U2") (pin "17") (pinfunction "IO19_17") (pintype "bidirectional"))
    )
    (net (code "16") (name "INT_RTC") (class "Default")
      (node (ref "R1_PINH1") (pin "1") (pinfunction "1_1") (pintype "passive"))
      (node (ref "TP15") (pin "TP") (pinfunction "TP_TP") (pintype "input"))
      (node (ref "U2") (pin "8") (pinfunction "IO0_8") (pintype "bidirectional"))
      (node (ref "U5") (pin "3") (pinfunction "SQW/~{INT}_3") (pintype "output"))
    )
    (net (code "17") (name "IO{slash}BOOT") (class "Default")
      (node (ref "BOOT_BUTTON") (pin "3") (pinfunction "3_3") (pintype "passive"))
      (node (ref "BOOT_BUTTON") (pin "4") (pinfunction "4_4") (pintype "passive"))
      (node (ref "C6") (pin "1") (pinfunction "1_1") (pintype "passive"))
      (node (ref "R_BOOT") (pin "2") (pinfunction "2_2") (pintype "passive"))
      (node (ref "U2") (pin "15") (pinfunction "IO9_15") (pintype "bidirectional"))
    )
    (net (code "18") (name "IO{slash}CHANGE") (class "Default")
      (node (ref "C10") (pin "1") (pinfunction "1_1") (pintype "passive"))
      (node (ref "CHANGE_BUTTON") (pin "3") (pinfunction "3_3") (pintype "passive"))
      (node (ref "CHANGE_BUTTON") (pin "4") (pinfunction "4_4") (pintype "passive"))
      (node (ref "R_CHANGE") (pin "2") (pinfunction "2_2") (pintype "passive"))
      (node (ref "U2") (pin "23") (pinfunction "IO15_23") (pintype "bidirectional"))
    )
    (net (code "19") (name "MISO") (class "Default")
      (node (ref "J4") (pin "P7") (pinfunction "DAT0_P7") (pintype "bidirectional"))
      (node (ref "TP6") (pin "TP") (pinfunction "TP_TP") (pintype "input"))
      (node (ref "U2") (pin "27") (pinfunction "IO2_27") (pintype "bidirectional"))
      (node (ref "U3") (pin "2") (pinfunction "DO(IO1)_2") (pintype "bidirectional"))
    )
    (net (code "20") (name "MOSI") (class "Default")
      (node (ref "J1") (pin "14") (pinfunction "14_14") (pintype "bidirectional"))
      (node (ref "J4") (pin "P3") (pinfunction "CMD_P3") (pintype "bidirectional"))
      (node (ref "TP7") (pin "TP") (pinfunction "TP_TP") (pintype "input"))
      (node (ref "U2") (pin "7") (pinfunction "IO7_7") (pintype "bidirectional"))
      (node (ref "U3") (pin "5") (pinfunction "DI(IO0)_5") (pintype "bidirectional"))
    )
    (net (code "21") (name "N$16") (class "Default")
      (node (ref "D8") (pin "2") (pinfunction "2_2") (pintype "passive"))
      (node (ref "R10") (pin "1") (pinfunction "1_1") (pintype "passive"))
    )
    (net (code "22") (name "N$17") (class "Default")
      (node (ref "D6") (pin "2") (pinfunction "2_2") (pintype "passive"))
      (node (ref "R9") (pin "1") (pinfunction "1_1") (pintype "passive"))
    )
    (net (code "23") (name "N$19") (class "Default")
      (node (ref "D9") (pin "2") (pinfunction "2_2") (pintype "passive"))
      (node (ref "R5") (pin "1") (pinfunction "1_1") (pintype "passive"))
    )
    (net (code "24") (name "N$20") (class "Default")
      (node (ref "D10") (pin "2") (pinfunction "2_2") (pintype "passive"))
      (node (ref "R6") (pin "1") (pinfunction "1_1") (pintype "passive"))
    )
    (net (code "25") (name "N$21") (class "Default")
      (node (ref "D11") (pin "2") (pinfunction "2_2") (pintype "passive"))
      (node (ref "R7") (pin "1") (pinfunction "1_1") (pintype "passive"))
    )
    (net (code "26") (name "N$22") (class "Default")
      (node (ref "D12") (pin "2") (pinfunction "2_2") (pintype "passive"))
      (node (ref "R8") (pin "1") (pinfunction "1_1") (pintype "passive"))
    )
    (net (code "27") (name "Net-(CHG_LED-PadC)") (class "Default")
      (node (ref "CHG_LED") (pin "C") (pinfunction "C_C") (pintype "passive"))
      (node (ref "R1_BAT") (pin "2") (pinfunction "2_2") (pintype "passive"))
    )
    (net (code "28") (name "Net-(D2-CATHODE)") (class "Default")
      (node (ref "C1_BAT1") (pin "1") (pinfunction "1_1") (pintype "passive"))
      (node (ref "D2") (pin "1") (pinfunction "CATHODE_1") (pintype "bidirectional"))
      (node (ref "IC4") (pin "1") (pinfunction "VIN_1") (pintype "bidirectional"))
      (node (ref "IC4") (pin "3") (pinfunction "CE_3") (pintype "bidirectional"))
      (node (ref "Q1") (pin "2") (pinfunction "S_2") (pintype "bidirectional"))
    )
    (net (code "29") (name "Net-(D3-A)") (class "Default")
      (node (ref "C4") (pin "1") (pinfunction "1_1") (pintype "passive"))
      (node (ref "D3") (pin "2") (pinfunction "A_2") (pintype "bidirectional"))
      (node (ref "D4") (pin "1") (pinfunction "K_1") (pintype "bidirectional"))
    )
    (net (code "30") (name "Net-(D7-CATHODE)") (class "Default")
      (node (ref "D7") (pin "1") (pinfunction "CATHODE_1") (pintype "bidirectional"))
      (node (ref "R_CAPACITOR") (pin "2") (pinfunction "2_2") (pintype "passive"))
    )
    (net (code "31") (name "Net-(EPD_C1-Pad1)") (class "Default")
      (node (ref "EPD_C1") (pin "1") (pinfunction "1_1") (pintype "passive"))
      (node (ref "J1") (pin "4") (pinfunction "4_4") (pintype "bidirectional"))
    )
    (net (code "32") (name "Net-(EPD_C2-Pad1)") (class "Default")
      (node (ref "EPD_C2") (pin "1") (pinfunction "1_1") (pintype "passive"))
      (node (ref "J1") (pin "5") (pinfunction "5_5") (pintype "bidirectional"))
    )
    (net (code "33") (name "Net-(EPD_C6-Pad1)") (class "Default")
      (node (ref "EPD_C6") (pin "1") (pinfunction "1_1") (pintype "passive"))
      (node (ref "J1") (pin "18") (pinfunction "18_18") (pintype "bidirectional"))
    )
    (net (code "34") (name "Net-(EPD_C7-Pad1)") (class "Default")
      (node (ref "EPD_C7") (pin "1") (pinfunction "1_1") (pintype "passive"))
      (node (ref "J1") (pin "19") (pinfunction "19_19") (pintype "bidirectional"))
    )
    (net (code "35") (name "Net-(EPD_C8-Pad1)") (class "Default")
      (node (ref "EPD_C8") (pin "1") (pinfunction "1_1") (pintype "passive"))
      (node (ref "J1") (pin "20") (pinfunction "20_20") (pintype "bidirectional"))
    )
    (net (code "36") (name "Net-(EPD_C10-Pad1)") (class "Default")
      (node (ref "EPD_C10") (pin "1") (pinfunction "1_1") (pintype "passive"))
      (node (ref "J1") (pin "22") (pinfunction "22_22") (pintype "bidirectional"))
    )
    (net (code "37") (name "Net-(EPD_C12-Pad1)") (class "Default")
      (node (ref "EPD_C12") (pin "1") (pinfunction "1_1") (pintype "passive"))
      (node (ref "J1") (pin "24") (pinfunction "24_24") (pintype "bidirectional"))
    )
    (net (code "38") (name "Net-(IC1-CT)") (class "Default")
      (node (ref "C_DELAY") (pin "1") (pinfunction "1_1") (pintype "passive"))
      (node (ref "IC1") (pin "5") (pinfunction "CT_5") (pintype "bidirectional"))
    )
    (net (code "39") (name "Net-(J2-PadA5)") (class "Default")
      (node (ref "J2") (pin "A5") (pinfunction "A5_A5") (pintype "bidirectional"))
      (node (ref "R2-USB1") (pin "2") (pinfunction "2_2") (pintype "passive"))
    )
    (net (code "40") (name "Net-(J2-PadB5)") (class "Default")
      (node (ref "J2") (pin "B5") (pinfunction "B5_B5") (pintype "bidirectional"))
      (node (ref "R2-USB") (pin "1") (pinfunction "1_1") (pintype "passive"))
    )
    (net (code "41") (name "Net-(U1-PROG)") (class "Default")
      (node (ref "R2_BAT") (pin "2") (pinfunction "2_2") (pintype "passive"))
      (node (ref "U1") (pin "5") (pinfunction "PROG_5") (pintype "input"))
    )
    (net (code "42") (name "Net-(U1-STAT)") (class "Default")
      (node (ref "R1_BAT") (pin "1") (pinfunction "1_1") (pintype "passive"))
      (node (ref "U1") (pin "1") (pinfunction "STAT_1") (pintype "output"))
    )
    (net (code "43") (name "PREVGH") (class "Default")
      (node (ref "D5") (pin "1") (pinfunction "K_1") (pintype "bidirectional"))
      (node (ref "EPD_C9") (pin "1") (pinfunction "1_1") (pintype "passive"))
      (node (ref "J1") (pin "21") (pinfunction "21_21") (pintype "bidirectional"))
    )
    (net (code "44") (name "PREVGL") (class "Default")
      (node (ref "D4") (pin "2") (pinfunction "A_2") (pintype "bidirectional"))
      (node (ref "EPD_C11") (pin "1") (pinfunction "1_1") (pintype "passive"))
      (node (ref "J1") (pin "23") (pinfunction "23_23") (pintype "bidirectional"))
    )
    (net (code "45") (name "RESE") (class "Default")
      (node (ref "J1") (pin "3") (pinfunction "3_3") (pintype "bidirectional"))
      (node (ref "Q3") (pin "2") (pinfunction "S_2") (pintype "bidirectional"))
      (node (ref "R3") (pin "1") (pinfunction "1_1") (pintype "passive"))
    )
    (net (code "46") (name "RESE'") (class "Default")
      (node (ref "R2") (pin "2") (pinfunction "2_2") (pintype "passive"))
      (node (ref "R3") (pin "2") (pinfunction "2_2") (pintype "passive"))
      (node (ref "SJ1") (pin "2") (pinfunction "2_2") (pintype "passive"))
    )
    (net (code "47") (name "RESET") (class "Default")
      (node (ref "C5") (pin "1") (pinfunction "1_1") (pintype "passive"))
      (node (ref "IC1") (pin "1") (pinfunction "VOUT_1") (pintype "bidirectional"))
      (node (ref "RESET_BUTTON") (pin "3") (pinfunction "3_3") (pintype "passive"))
      (node (ref "RESET_BUTTON") (pin "4") (pinfunction "4_4") (pintype "passive"))
      (node (ref "R_RESET") (pin "2") (pinfunction "2_2") (pintype "passive"))
      (node (ref "U2") (pin "3") (pinfunction "EN_3") (pintype "input"))
    )
    (net (code "48") (name "RTC_RST") (class "Default")
      (node (ref "U2") (pin "16") (pinfunction "IO18_16") (pintype "bidirectional"))
      (node (ref "U5") (pin "4") (pinfunction "~{RST}_4") (pintype "input"))
    )
    (net (code "49") (name "RX") (class "Default")
      (node (ref "TP2") (pin "TP") (pinfunction "TP_TP") (pintype "input"))
      (node (ref "U2") (pin "24") (pinfunction "RXD0/GPIO17_24") (pintype "bidirectional"))
    )
    (net (code "50") (name "SCK") (class "Default")
      (node (ref "J1") (pin "13") (pinfunction "13_13") (pintype "bidirectional"))
      (node (ref "J4") (pin "P5") (pinfunction "CLK_P5") (pintype "bidirectional"))
      (node (ref "TP8") (pin "TP") (pinfunction "TP_TP") (pintype "input"))
      (node (ref "U2") (pin "6") (pinfunction "IO6_6") (pintype "bidirectional"))
      (node (ref "U3") (pin "6") (pinfunction "CLK_6") (pintype "input"))
    )
    (net (code "51") (name "SCL") (class "Default")
      (node (ref "J3") (pin "4") (pinfunction "4_4") (pintype "passive"))
      (node (ref "R2-PINH") (pin "1") (pinfunction "1_1") (pintype "passive"))
      (node (ref "SENSOR2") (pin "4") (pinfunction "SCK_4") (pintype "input"))
      (node (ref "U2") (pin "20") (pinfunction "IO22_20") (pintype "bidirectional"))
      (node (ref "U4") (pin "7") (pinfunction "SCL_7") (pintype "input"))
      (node (ref "U5") (pin "16") (pinfunction "SCL_16") (pintype "input"))
    )
    (net (code "52") (name "SDA") (class "Default")
      (node (ref "J3") (pin "3") (pinfunction "3_3") (pintype "passive"))
      (node (ref "R1_PINH") (pin "1") (pinfunction "1_1") (pintype "passive"))
      (node (ref "SENSOR2") (pin "3") (pinfunction "SDI_3") (pintype "bidirectional"))
      (node (ref "U2") (pin "19") (pinfunction "IO21_19") (pintype "bidirectional"))
      (node (ref "U4") (pin "8") (pinfunction "SDA_8") (pintype "bidirectional"))
      (node (ref "U5") (pin "15") (pinfunction "SDA_15") (pintype "bidirectional"))
    )
    (net (code "53") (name "SRC") (class "Default")
      (node (ref "C4") (pin "2") (pinfunction "2_2") (pintype "passive"))
      (node (ref "D5") (pin "2") (pinfunction "A_2") (pintype "bidirectional"))
      (node (ref "L1") (pin "1") (pinfunction "1_1") (pintype "passive"))
      (node (ref "Q3") (pin "3") (pinfunction "D_3") (pintype "bidirectional"))
    )
    (net (code "54") (name "SS_SD") (class "Default")
      (node (ref "J4") (pin "P2") (pinfunction "CD/DAT3_P2") (pintype "bidirectional"))
      (node (ref "U2") (pin "4") (pinfunction "IO4_4") (pintype "bidirectional"))
    )
    (net (code "55") (name "TX") (class "Default")
      (node (ref "TP1") (pin "TP") (pinfunction "TP_TP") (pintype "input"))
      (node (ref "U2") (pin "25") (pinfunction "TXD0/GPIO16_25") (pintype "bidirectional"))
    )
    (net (code "56") (name "USB_D+") (class "Default")
      (node (ref "D1") (pin "1") (pinfunction "I/O1_1_1") (pintype "bidirectional"))
      (node (ref "U2") (pin "14") (pinfunction "IO13_14") (pintype "bidirectional"))
    )
    (net (code "57") (name "USB_D-") (class "Default")
      (node (ref "D1") (pin "3") (pinfunction "I/O2_1_3") (pintype "bidirectional"))
      (node (ref "U2") (pin "13") (pinfunction "IO12_13") (pintype "bidirectional"))
    )
    (net (code "58") (name "VBAT") (class "Default")
      (node (ref "C2_BAT") (pin "1") (pinfunction "1_1") (pintype "passive"))
      (node (ref "Q1") (pin "3") (pinfunction "D_3") (pintype "bidirectional"))
      (node (ref "TP3") (pin "TP") (pinfunction "TP_TP") (pintype "input"))
      (node (ref "U1") (pin "3") (pinfunction "VBAT_3") (pintype "power_in"))
      (node (ref "U4") (pin "2") (pinfunction "CELL_2") (pintype "power_in"))
      (node (ref "U4") (pin "3") (pinfunction "VDD_3") (pintype "power_in"))
    )
    (net (code "59") (name "VBUS") (class "Default")
      (node (ref "C1_BAT") (pin "1") (pinfunction "1_1") (pintype "passive"))
      (node (ref "C4_USB") (pin "1") (pinfunction "1_1") (pintype "passive"))
      (node (ref "C5_USB") (pin "1") (pinfunction "1_1") (pintype "passive"))
      (node (ref "CHG_LED") (pin "A") (pinfunction "A_A") (pintype "passive"))
      (node (ref "D1") (pin "5") (pinfunction "VBUS_5") (pintype "bidirectional"))
      (node (ref "D2") (pin "2") (pinfunction "ANODE_2") (pintype "bidirectional"))
      (node (ref "PFMF.050.1") (pin "2") (pinfunction "2_2") (pintype "passive"))
      (node (ref "Q1") (pin "1") (pinfunction "G_1") (pintype "bidirectional"))
      (node (ref "R1_PWRUSB") (pin "2") (pinfunction "2_2") (pintype "passive"))
      (node (ref "TP14") (pin "TP") (pinfunction "TP_TP") (pintype "input"))
      (node (ref "U1") (pin "4") (pinfunction "VIN_4") (pintype "power_in"))
    )
    (net (code "60") (name "VRTC") (class "Default")
      (node (ref "C10_SUPERCAP") (pin "2") (pinfunction "2_2") (pintype "passive"))
      (node (ref "C8") (pin "1") (pinfunction "1_1") (pintype "passive"))
      (node (ref "R_CAPACITOR") (pin "1") (pinfunction "1_1") (pintype "passive"))
      (node (ref "U5") (pin "14") (pinfunction "VBAT_14") (pintype "power_in"))
    )
    (net (code "61") (name "VUSB") (class "Default")
      (node (ref "J2") (pin "A4") (pinfunction "A4_A4") (pintype "bidirectional"))
      (node (ref "J2") (pin "A9") (pinfunction "A9_A9") (pintype "bidirectional"))
      (node (ref "J2") (pin "B4") (pinfunction "B4_B4") (pintype "bidirectional"))
      (node (ref "J2") (pin "B9") (pinfunction "B9_B9") (pintype "bidirectional"))
      (node (ref "PFMF.050.1") (pin "1") (pinfunction "1_1") (pintype "passive"))
    )
    (net (code "62") (name "unconnected-(IC1-NC-Pad4)") (class "Default")
      (node (ref "IC1") (pin "4") (pinfunction "NC_4") (pintype "no_connect"))
    )
    (net (code "63") (name "unconnected-(IC4-NC-Pad4)") (class "Default")
      (node (ref "IC4") (pin "4") (pinfunction "NC_4") (pintype "no_connect"))
    )
    (net (code "64") (name "unconnected-(J1-Pad1)") (class "Default")
      (node (ref "J1") (pin "1") (pinfunction "1_1") (pintype "bidirectional"))
    )
    (net (code "65") (name "unconnected-(J1-Pad6)") (class "Default")
      (node (ref "J1") (pin "6") (pinfunction "6_6") (pintype "bidirectional"))
    )
    (net (code "66") (name "unconnected-(J1-Pad7)") (class "Default")
      (node (ref "J1") (pin "7") (pinfunction "7_7") (pintype "bidirectional"))
    )
    (net (code "67") (name "unconnected-(J2-PadA8)") (class "Default")
      (node (ref "J2") (pin "A8") (pinfunction "A8_A8") (pintype "bidirectional"))
    )
    (net (code "68") (name "unconnected-(J2-PadB8)") (class "Default")
      (node (ref "J2") (pin "B8") (pinfunction "B8_B8") (pintype "bidirectional"))
    )
    (net (code "69") (name "unconnected-(J4-DAT1-PadP8)") (class "Default")
      (node (ref "J4") (pin "P8") (pinfunction "DAT1_P8") (pintype "bidirectional"))
    )
    (net (code "70") (name "unconnected-(J4-DAT2-PadP1)") (class "Default")
      (node (ref "J4") (pin "P1") (pinfunction "DAT2_P1") (pintype "bidirectional"))
    )
    (net (code "71") (name "unconnected-(J4-DETECTION_1-PadS1)") (class "Default")
      (node (ref "J4") (pin "S1") (pinfunction "DETECTION_1_S1") (pintype "bidirectional"))
    )
    (net (code "72") (name "unconnected-(J4-DETECTION_2-PadS2)") (class "Default")
      (node (ref "J4") (pin "S2") (pinfunction "DETECTION_2_S2") (pintype "bidirectional"))
    )
    (net (code "73") (name "unconnected-(U2-NC-Pad22)") (class "Default")
      (node (ref "U2") (pin "22") (pinfunction "NC_22") (pintype "no_connect"))
    )
    (net (code "74") (name "unconnected-(U4-~{ALERT}-Pad5)") (class "Default")
      (node (ref "U4") (pin "5") (pinfunction "~{ALERT}_5") (pintype "output"))
    )
  )
)
